# ConnectBox_Charger.net
KiCad netlist of a schematic drawn in EAGLE
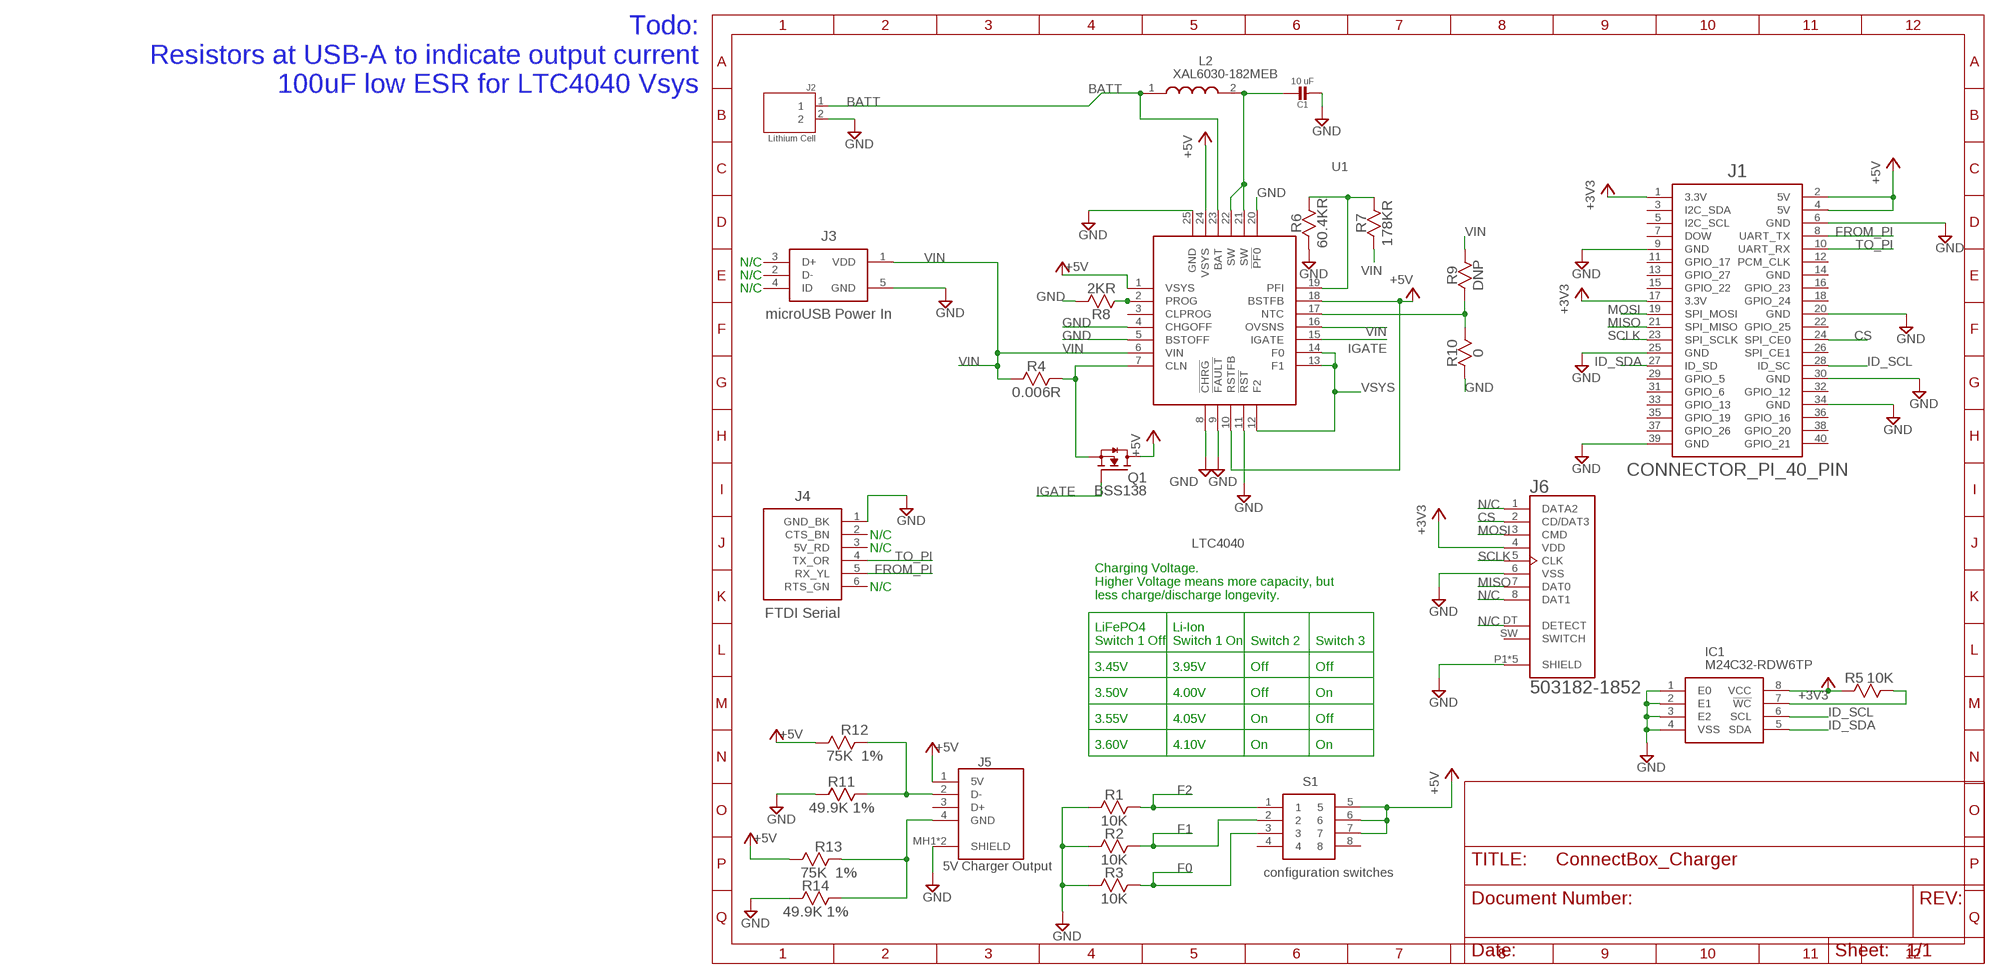
[diagram p0: schematic, sheet 1]

(export (version "E")
  (design (tool "Eeschema 10.0.6"))
  (components
    (comp (ref "C1")
      (value "10 uF")
      (footprint "eagle-import:MICROBUILDER_0805_10MGAP")
      (libsource (lib "eagle-import") (part "MICROBUILDER_CAP_CERAMIC0805_10MGAP"))
    )
    (comp (ref "IC1")
      (value "M24C32-RDW6TP")
      (footprint "eagle-import:SOP65P640X120-8N")
      (fields (field (name "MOUSER_PART_NUMBER") "511-M24C32-RDW6TP"))
      (libsource (lib "eagle-import") (part "M24C32-RDW6TP"))
    )
    (comp (ref "J1")
      (value "CONNECTOR_PI_40_PIN")
      (footprint "eagle-import:2X20")
      (libsource (lib "eagle-import") (part "CONNECTOR_PI_40_PIN"))
    )
    (comp (ref "J2")
      (value "Lithium Cell")
      (footprint "eagle-import:JST_S2B-PH-SM4-TB(LF)(SN)")
      (fields (field (name "MF") "JST Sales") (field (name "MP") "S2B-PH-SM4-TB_LF__SN_"))
      (libsource (lib "eagle-import") (part "S2B-PH-SM4-TB(LF)(SN)"))
    )
    (comp (ref "J3")
      (value "microUSB Power In")
      (footprint "eagle-import:FRAMATOME_10118194-0001LF")
      (fields (field (name "MF") "FCI") (field (name "MP") "10118194-0001LF"))
      (libsource (lib "eagle-import") (part "10118194-0001LF"))
    )
    (comp (ref "J4")
      (value "FTDI Serial")
      (footprint "eagle-import:ESQ-106-XX-X-S")
      (libsource (lib "eagle-import") (part "CONNECTOR-6-FTDI"))
    )
    (comp (ref "J5")
      (value "5V Charger Output")
      (footprint "eagle-import:SS52100001")
      (fields
        (field (name "MANUFACTURER_PART_NUMBER") "SS-52100-001")
        (field (name "MOUSER_PART_NUMBER") "530-SS-52100-001")
      )
      (libsource (lib "eagle-import") (part "SS-52100-001"))
    )
    (comp (ref "J6")
      (value "503182-1852")
      (footprint "eagle-import:MOLEX_503182-1852")
      (fields
        (field (name "DIGI-KEY_PART_NUMBER") "WM12834CT-ND")
        (field (name "MF") "Molex")
        (field (name "MP") "5031821852")
      )
      (libsource (lib "eagle-import") (part "503182-1852"))
    )
    (comp (ref "L2")
      (value "XAL6030-182MEB")
      (footprint "eagle-import:XAL6030182MEB")
      (fields (field (name "MOUSER_PART_NUMBER") "994-XAL6030-182MEB"))
      (libsource (lib "eagle-import") (part "XAL6030-182MEB"))
    )
    (comp (ref "Q1")
      (value "BSS138")
      (footprint "eagle-import:BSS138")
      (fields (field (name "MF") "Fairchild Semiconductor"))
      (libsource (lib "eagle-import") (part "BSS138"))
    )
    (comp (ref "R1")
      (value "10K")
      (footprint "eagle-import:RESC1608X55L25N")
      (libsource (lib "eagle-import") (part "RESISTOR0603"))
    )
    (comp (ref "R2")
      (value "10K")
      (footprint "eagle-import:RESC1608X55L25N")
      (libsource (lib "eagle-import") (part "RESISTOR0603"))
    )
    (comp (ref "R3")
      (value "10K")
      (footprint "eagle-import:RESC1608X55L25N")
      (libsource (lib "eagle-import") (part "RESISTOR0603"))
    )
    (comp (ref "R4")
      (value "0.006R")
      (footprint "eagle-import:RESC1608X55L25N")
      (libsource (lib "eagle-import") (part "RESISTOR0603"))
    )
    (comp (ref "R5")
      (value "10K")
      (footprint "eagle-import:RESC1608X55L25N")
      (libsource (lib "eagle-import") (part "RESISTOR0603"))
    )
    (comp (ref "R6")
      (value "60.4KR")
      (footprint "eagle-import:RESC1608X55L25N")
      (libsource (lib "eagle-import") (part "RESISTOR0603"))
    )
    (comp (ref "R7")
      (value "178KR")
      (footprint "eagle-import:RESC1608X55L25N")
      (libsource (lib "eagle-import") (part "RESISTOR0603"))
    )
    (comp (ref "R8")
      (value "2KR")
      (footprint "eagle-import:RESC1608X55L25N")
      (libsource (lib "eagle-import") (part "RESISTOR0603"))
    )
    (comp (ref "R9")
      (value "DNP")
      (footprint "eagle-import:RESC1608X55L25N")
      (libsource (lib "eagle-import") (part "RESISTOR0603"))
    )
    (comp (ref "R10")
      (value "0")
      (footprint "eagle-import:RESC1608X55L25N")
      (libsource (lib "eagle-import") (part "RESISTOR0603"))
    )
    (comp (ref "R11")
      (value "49.9K 1%")
      (footprint "eagle-import:RESC1608X55L25N")
      (libsource (lib "eagle-import") (part "RESISTOR0603"))
    )
    (comp (ref "R12")
      (value "75K 1%")
      (footprint "eagle-import:RESC1608X55L25N")
      (libsource (lib "eagle-import") (part "RESISTOR0603"))
    )
    (comp (ref "R13")
      (value "75K 1%")
      (footprint "eagle-import:RESC1608X55L25N")
      (libsource (lib "eagle-import") (part "RESISTOR0603"))
    )
    (comp (ref "R14")
      (value "49.9K 1%")
      (footprint "eagle-import:RESC1608X55L25N")
      (libsource (lib "eagle-import") (part "RESISTOR0603"))
    )
    (comp (ref "S1")
      (value "configuration switches")
      (footprint "eagle-import:219-4LPST")
      (fields
        (field (name "MANUFACTURER_PART_NUMBER") "219-4LPST")
        (field (name "MOUSER_PART_NUMBER") "774-2194LPST")
        (field (name "RS_PART_NUMBER") "1774220")
      )
      (libsource (lib "eagle-import") (part "219-4LPST"))
    )
    (comp (ref "U1")
      (value "LTC4040")
      (footprint "eagle-import:QFN50P500X400X80-25N")
      (libsource (lib "eagle-import") (part "LTC4040"))
    )
  )
  (nets
    (net (code "1") (name "+3V3") (class "Default")
      (node (ref "IC1") (pin "8") (pinfunction "VCC_8") (pintype "bidirectional"))
      (node (ref "J1") (pin "1") (pinfunction "3.3V_1") (pintype "bidirectional"))
      (node (ref "J1") (pin "17") (pinfunction "3.3V_17") (pintype "bidirectional"))
      (node (ref "J6") (pin "4") (pinfunction "VDD_4") (pintype "power_in"))
      (node (ref "R5") (pin "2") (pinfunction "2_2") (pintype "bidirectional"))
    )
    (net (code "2") (name "+5V") (class "Default")
      (node (ref "J1") (pin "2") (pinfunction "5V_2") (pintype "bidirectional"))
      (node (ref "J1") (pin "4") (pinfunction "5V_4") (pintype "bidirectional"))
      (node (ref "J5") (pin "1") (pinfunction "5V_1") (pintype "bidirectional"))
      (node (ref "Q1") (pin "D") (pinfunction "D_D") (pintype "passive"))
      (node (ref "R12") (pin "2") (pinfunction "2_2") (pintype "bidirectional"))
      (node (ref "R13") (pin "2") (pinfunction "2_2") (pintype "bidirectional"))
      (node (ref "S1") (pin "5") (pinfunction "5_5") (pintype "bidirectional"))
      (node (ref "S1") (pin "6") (pinfunction "6_6") (pintype "bidirectional"))
      (node (ref "S1") (pin "7") (pinfunction "7_7") (pintype "bidirectional"))
      (node (ref "U1") (pin "1") (pinfunction "VSYS_1") (pintype "bidirectional"))
      (node (ref "U1") (pin "10") (pinfunction "RSTFB_10") (pintype "bidirectional"))
      (node (ref "U1") (pin "18") (pinfunction "BSTFB_18") (pintype "bidirectional"))
      (node (ref "U1") (pin "24") (pinfunction "VSYS_24") (pintype "bidirectional"))
    )
    (net (code "3") (name "/BATT") (class "Default")
      (node (ref "J2") (pin "1") (pinfunction "1_1") (pintype "passive"))
      (node (ref "L2") (pin "1") (pinfunction "1_1") (pintype "bidirectional"))
      (node (ref "U1") (pin "23") (pinfunction "BAT_23") (pintype "bidirectional"))
    )
    (net (code "4") (name "/CS") (class "Default")
      (node (ref "J1") (pin "24") (pinfunction "SPI_CE0_24") (pintype "bidirectional"))
      (node (ref "J6") (pin "2") (pinfunction "CD/DAT3_2") (pintype "bidirectional"))
    )
    (net (code "5") (name "/F0") (class "Default")
      (node (ref "R3") (pin "2") (pinfunction "2_2") (pintype "bidirectional"))
      (node (ref "S1") (pin "3") (pinfunction "3_3") (pintype "bidirectional"))
    )
    (net (code "6") (name "/F1") (class "Default")
      (node (ref "R2") (pin "2") (pinfunction "2_2") (pintype "bidirectional"))
      (node (ref "S1") (pin "2") (pinfunction "2_2") (pintype "bidirectional"))
    )
    (net (code "7") (name "/F2") (class "Default")
      (node (ref "R1") (pin "2") (pinfunction "2_2") (pintype "bidirectional"))
      (node (ref "S1") (pin "1") (pinfunction "1_1") (pintype "bidirectional"))
    )
    (net (code "8") (name "/FROM_PI") (class "Default")
      (node (ref "J1") (pin "8") (pinfunction "UART_TX_8") (pintype "bidirectional"))
      (node (ref "J4") (pin "5") (pinfunction "RX_YL_5") (pintype "bidirectional"))
    )
    (net (code "9") (name "/ID_SCL") (class "Default")
      (node (ref "IC1") (pin "6") (pinfunction "SCL_6") (pintype "bidirectional"))
      (node (ref "J1") (pin "28") (pinfunction "ID_SC_28") (pintype "bidirectional"))
    )
    (net (code "10") (name "/ID_SDA") (class "Default")
      (node (ref "IC1") (pin "5") (pinfunction "SDA_5") (pintype "bidirectional"))
      (node (ref "J1") (pin "27") (pinfunction "ID_SD_27") (pintype "bidirectional"))
    )
    (net (code "11") (name "/IGATE") (class "Default")
      (node (ref "Q1") (pin "G") (pinfunction "G_G") (pintype "passive"))
      (node (ref "U1") (pin "15") (pinfunction "IGATE_15") (pintype "bidirectional"))
    )
    (net (code "12") (name "/MISO") (class "Default")
      (node (ref "J1") (pin "21") (pinfunction "SPI_MISO_21") (pintype "bidirectional"))
      (node (ref "J6") (pin "7") (pinfunction "DAT0_7") (pintype "bidirectional"))
    )
    (net (code "13") (name "/MOSI") (class "Default")
      (node (ref "J1") (pin "19") (pinfunction "SPI_MOSI_19") (pintype "bidirectional"))
      (node (ref "J6") (pin "3") (pinfunction "CMD_3") (pintype "bidirectional"))
    )
    (net (code "14") (name "/N{slash}C") (class "Default")
      (node (ref "J6") (pin "1") (pinfunction "DATA2_1") (pintype "bidirectional"))
      (node (ref "J6") (pin "8") (pinfunction "DAT1_8") (pintype "bidirectional"))
      (node (ref "J6") (pin "DT") (pinfunction "DETECT_DT") (pintype "bidirectional"))
    )
    (net (code "15") (name "/SCLK") (class "Default")
      (node (ref "J1") (pin "23") (pinfunction "SPI_SCLK_23") (pintype "bidirectional"))
      (node (ref "J6") (pin "5") (pinfunction "CLK_5") (pintype "bidirectional"))
    )
    (net (code "16") (name "/TO_PI") (class "Default")
      (node (ref "J1") (pin "10") (pinfunction "UART_RX_10") (pintype "bidirectional"))
      (node (ref "J4") (pin "4") (pinfunction "TX_OR_4") (pintype "bidirectional"))
    )
    (net (code "17") (name "/VIN") (class "Default")
      (node (ref "J3") (pin "1") (pinfunction "VDD_1") (pintype "power_in"))
      (node (ref "R4") (pin "1") (pinfunction "1_1") (pintype "bidirectional"))
      (node (ref "R7") (pin "1") (pinfunction "1_1") (pintype "bidirectional"))
      (node (ref "R9") (pin "2") (pinfunction "2_2") (pintype "bidirectional"))
      (node (ref "U1") (pin "16") (pinfunction "OVSNS_16") (pintype "bidirectional"))
      (node (ref "U1") (pin "6") (pinfunction "VIN_6") (pintype "bidirectional"))
    )
    (net (code "18") (name "/VSYS") (class "Default")
      (node (ref "U1") (pin "12") (pinfunction "F2_12") (pintype "bidirectional"))
      (node (ref "U1") (pin "13") (pinfunction "F1_13") (pintype "bidirectional"))
      (node (ref "U1") (pin "14") (pinfunction "F0_14") (pintype "bidirectional"))
    )
    (net (code "19") (name "GND") (class "Default")
      (node (ref "C1") (pin "2") (pinfunction "2_2") (pintype "passive"))
      (node (ref "IC1") (pin "1") (pinfunction "E0_1") (pintype "bidirectional"))
      (node (ref "IC1") (pin "2") (pinfunction "E1_2") (pintype "bidirectional"))
      (node (ref "IC1") (pin "3") (pinfunction "E2_3") (pintype "bidirectional"))
      (node (ref "IC1") (pin "4") (pinfunction "VSS_4") (pintype "bidirectional"))
      (node (ref "J1") (pin "20") (pinfunction "GND_20") (pintype "bidirectional"))
      (node (ref "J1") (pin "25") (pinfunction "GND_25") (pintype "bidirectional"))
      (node (ref "J1") (pin "30") (pinfunction "GND_30") (pintype "bidirectional"))
      (node (ref "J1") (pin "34") (pinfunction "GND_34") (pintype "bidirectional"))
      (node (ref "J1") (pin "39") (pinfunction "GND_39") (pintype "bidirectional"))
      (node (ref "J1") (pin "6") (pinfunction "GND_6") (pintype "bidirectional"))
      (node (ref "J1") (pin "9") (pinfunction "GND_9") (pintype "bidirectional"))
      (node (ref "J2") (pin "2") (pinfunction "2_2") (pintype "passive"))
      (node (ref "J3") (pin "5") (pinfunction "GND_5") (pintype "power_in"))
      (node (ref "J4") (pin "1") (pinfunction "GND_BK_1") (pintype "bidirectional"))
      (node (ref "J5") (pin "MH1") (pinfunction "SHIELD_MH1") (pintype "bidirectional"))
      (node (ref "J5") (pin "MH2") (pinfunction "SHIELD_MH2") (pintype "bidirectional"))
      (node (ref "J6") (pin "6") (pinfunction "VSS_6") (pintype "power_in"))
      (node (ref "J6") (pin "P1") (pinfunction "SHIELD_P1") (pintype "passive"))
      (node (ref "J6") (pin "P2") (pinfunction "SHIELD_P2") (pintype "passive"))
      (node (ref "J6") (pin "P3") (pinfunction "SHIELD_P3") (pintype "passive"))
      (node (ref "J6") (pin "P4") (pinfunction "SHIELD_P4") (pintype "passive"))
      (node (ref "J6") (pin "P5") (pinfunction "SHIELD_P5") (pintype "passive"))
      (node (ref "R1") (pin "1") (pinfunction "1_1") (pintype "bidirectional"))
      (node (ref "R10") (pin "1") (pinfunction "1_1") (pintype "bidirectional"))
      (node (ref "R11") (pin "2") (pinfunction "2_2") (pintype "bidirectional"))
      (node (ref "R14") (pin "2") (pinfunction "2_2") (pintype "bidirectional"))
      (node (ref "R2") (pin "1") (pinfunction "1_1") (pintype "bidirectional"))
      (node (ref "R3") (pin "1") (pinfunction "1_1") (pintype "bidirectional"))
      (node (ref "R6") (pin "1") (pinfunction "1_1") (pintype "bidirectional"))
      (node (ref "R8") (pin "2") (pinfunction "2_2") (pintype "bidirectional"))
      (node (ref "U1") (pin "11") (pinfunction "~{RST}_11") (pintype "bidirectional"))
      (node (ref "U1") (pin "20") (pinfunction "~{PF0}_20") (pintype "bidirectional"))
      (node (ref "U1") (pin "25") (pinfunction "GND_25") (pintype "bidirectional"))
      (node (ref "U1") (pin "4") (pinfunction "CHGOFF_4") (pintype "bidirectional"))
      (node (ref "U1") (pin "5") (pinfunction "BSTOFF_5") (pintype "bidirectional"))
      (node (ref "U1") (pin "8") (pinfunction "~{CHRG}_8") (pintype "bidirectional"))
      (node (ref "U1") (pin "9") (pinfunction "~{FAULT}_9") (pintype "bidirectional"))
    )
    (net (code "20") (name "Net-(C1-Pad1)") (class "Default")
      (node (ref "C1") (pin "1") (pinfunction "1_1") (pintype "passive"))
      (node (ref "L2") (pin "2") (pinfunction "2_2") (pintype "bidirectional"))
      (node (ref "U1") (pin "21") (pinfunction "SW_21") (pintype "bidirectional"))
      (node (ref "U1") (pin "22") (pinfunction "SW_22") (pintype "bidirectional"))
    )
    (net (code "21") (name "Net-(IC1-~{WC})") (class "Default")
      (node (ref "IC1") (pin "7") (pinfunction "~{WC}_7") (pintype "bidirectional"))
      (node (ref "R5") (pin "1") (pinfunction "1_1") (pintype "bidirectional"))
    )
    (net (code "22") (name "Net-(J5-D-)") (class "Default")
      (node (ref "J5") (pin "2") (pinfunction "D-_2") (pintype "bidirectional"))
      (node (ref "R11") (pin "1") (pinfunction "1_1") (pintype "bidirectional"))
      (node (ref "R12") (pin "1") (pinfunction "1_1") (pintype "bidirectional"))
    )
    (net (code "23") (name "Net-(J5-GND)") (class "Default")
      (node (ref "J5") (pin "4") (pinfunction "GND_4") (pintype "bidirectional"))
      (node (ref "R13") (pin "1") (pinfunction "1_1") (pintype "bidirectional"))
      (node (ref "R14") (pin "1") (pinfunction "1_1") (pintype "bidirectional"))
    )
    (net (code "24") (name "Net-(U1-CLN)") (class "Default")
      (node (ref "Q1") (pin "S") (pinfunction "S_S") (pintype "passive"))
      (node (ref "R4") (pin "2") (pinfunction "2_2") (pintype "bidirectional"))
      (node (ref "U1") (pin "7") (pinfunction "CLN_7") (pintype "bidirectional"))
    )
    (net (code "25") (name "Net-(U1-NTC)") (class "Default")
      (node (ref "R10") (pin "2") (pinfunction "2_2") (pintype "bidirectional"))
      (node (ref "R9") (pin "1") (pinfunction "1_1") (pintype "bidirectional"))
      (node (ref "U1") (pin "17") (pinfunction "NTC_17") (pintype "bidirectional"))
    )
    (net (code "26") (name "Net-(U1-PFI)") (class "Default")
      (node (ref "R6") (pin "2") (pinfunction "2_2") (pintype "bidirectional"))
      (node (ref "R7") (pin "2") (pinfunction "2_2") (pintype "bidirectional"))
      (node (ref "U1") (pin "19") (pinfunction "PFI_19") (pintype "bidirectional"))
    )
    (net (code "27") (name "Net-(U1-PROG)") (class "Default")
      (node (ref "R8") (pin "1") (pinfunction "1_1") (pintype "bidirectional"))
      (node (ref "U1") (pin "2") (pinfunction "PROG_2") (pintype "bidirectional"))
    )
    (net (code "28") (name "unconnected-(J1-DOW-Pad7)") (class "Default")
      (node (ref "J1") (pin "7") (pinfunction "DOW_7") (pintype "bidirectional"))
    )
    (net (code "29") (name "unconnected-(J1-GND-Pad14)") (class "Default")
      (node (ref "J1") (pin "14") (pinfunction "GND_14") (pintype "bidirectional"))
    )
    (net (code "30") (name "unconnected-(J1-GPIO_5-Pad29)") (class "Default")
      (node (ref "J1") (pin "29") (pinfunction "GPIO_5_29") (pintype "bidirectional"))
    )
    (net (code "31") (name "unconnected-(J1-GPIO_6-Pad31)") (class "Default")
      (node (ref "J1") (pin "31") (pinfunction "GPIO_6_31") (pintype "bidirectional"))
    )
    (net (code "32") (name "unconnected-(J1-GPIO_12-Pad32)") (class "Default")
      (node (ref "J1") (pin "32") (pinfunction "GPIO_12_32") (pintype "bidirectional"))
    )
    (net (code "33") (name "unconnected-(J1-GPIO_13-Pad33)") (class "Default")
      (node (ref "J1") (pin "33") (pinfunction "GPIO_13_33") (pintype "bidirectional"))
    )
    (net (code "34") (name "unconnected-(J1-GPIO_16-Pad36)") (class "Default")
      (node (ref "J1") (pin "36") (pinfunction "GPIO_16_36") (pintype "bidirectional"))
    )
    (net (code "35") (name "unconnected-(J1-GPIO_17-Pad11)") (class "Default")
      (node (ref "J1") (pin "11") (pinfunction "GPIO_17_11") (pintype "bidirectional"))
    )
    (net (code "36") (name "unconnected-(J1-GPIO_19-Pad35)") (class "Default")
      (node (ref "J1") (pin "35") (pinfunction "GPIO_19_35") (pintype "bidirectional"))
    )
    (net (code "37") (name "unconnected-(J1-GPIO_20-Pad38)") (class "Default")
      (node (ref "J1") (pin "38") (pinfunction "GPIO_20_38") (pintype "bidirectional"))
    )
    (net (code "38") (name "unconnected-(J1-GPIO_21-Pad40)") (class "Default")
      (node (ref "J1") (pin "40") (pinfunction "GPIO_21_40") (pintype "bidirectional"))
    )
    (net (code "39") (name "unconnected-(J1-GPIO_22-Pad15)") (class "Default")
      (node (ref "J1") (pin "15") (pinfunction "GPIO_22_15") (pintype "bidirectional"))
    )
    (net (code "40") (name "unconnected-(J1-GPIO_23-Pad16)") (class "Default")
      (node (ref "J1") (pin "16") (pinfunction "GPIO_23_16") (pintype "bidirectional"))
    )
    (net (code "41") (name "unconnected-(J1-GPIO_24-Pad18)") (class "Default")
      (node (ref "J1") (pin "18") (pinfunction "GPIO_24_18") (pintype "bidirectional"))
    )
    (net (code "42") (name "unconnected-(J1-GPIO_25-Pad22)") (class "Default")
      (node (ref "J1") (pin "22") (pinfunction "GPIO_25_22") (pintype "bidirectional"))
    )
    (net (code "43") (name "unconnected-(J1-GPIO_26-Pad37)") (class "Default")
      (node (ref "J1") (pin "37") (pinfunction "GPIO_26_37") (pintype "bidirectional"))
    )
    (net (code "44") (name "unconnected-(J1-GPIO_27-Pad13)") (class "Default")
      (node (ref "J1") (pin "13") (pinfunction "GPIO_27_13") (pintype "bidirectional"))
    )
    (net (code "45") (name "unconnected-(J1-I2C_SCL-Pad5)") (class "Default")
      (node (ref "J1") (pin "5") (pinfunction "I2C_SCL_5") (pintype "bidirectional"))
    )
    (net (code "46") (name "unconnected-(J1-I2C_SDA-Pad3)") (class "Default")
      (node (ref "J1") (pin "3") (pinfunction "I2C_SDA_3") (pintype "bidirectional"))
    )
    (net (code "47") (name "unconnected-(J1-PCM_CLK-Pad12)") (class "Default")
      (node (ref "J1") (pin "12") (pinfunction "PCM_CLK_12") (pintype "bidirectional"))
    )
    (net (code "48") (name "unconnected-(J1-SPI_CE1-Pad26)") (class "Default")
      (node (ref "J1") (pin "26") (pinfunction "SPI_CE1_26") (pintype "bidirectional"))
    )
    (net (code "49") (name "unconnected-(J3-D+-Pad3)") (class "Default")
      (node (ref "J3") (pin "3") (pinfunction "D+_3") (pintype "bidirectional"))
    )
    (net (code "50") (name "unconnected-(J3-D--Pad2)") (class "Default")
      (node (ref "J3") (pin "2") (pinfunction "D-_2") (pintype "bidirectional"))
    )
    (net (code "51") (name "unconnected-(J3-ID-Pad4)") (class "Default")
      (node (ref "J3") (pin "4") (pinfunction "ID_4") (pintype "passive"))
    )
    (net (code "52") (name "unconnected-(J4-5V_RD-Pad3)") (class "Default")
      (node (ref "J4") (pin "3") (pinfunction "5V_RD_3") (pintype "bidirectional"))
    )
    (net (code "53") (name "unconnected-(J4-CTS_BN-Pad2)") (class "Default")
      (node (ref "J4") (pin "2") (pinfunction "CTS_BN_2") (pintype "bidirectional"))
    )
    (net (code "54") (name "unconnected-(J4-RTS_GN-Pad6)") (class "Default")
      (node (ref "J4") (pin "6") (pinfunction "RTS_GN_6") (pintype "bidirectional"))
    )
    (net (code "55") (name "unconnected-(J5-D+-Pad3)") (class "Default")
      (node (ref "J5") (pin "3") (pinfunction "D+_3") (pintype "bidirectional"))
    )
    (net (code "56") (name "unconnected-(J6-SWITCH-PadSW)") (class "Default")
      (node (ref "J6") (pin "SW") (pinfunction "SWITCH_SW") (pintype "bidirectional"))
    )
    (net (code "57") (name "unconnected-(S1-Pad4)") (class "Default")
      (node (ref "S1") (pin "4") (pinfunction "4_4") (pintype "bidirectional"))
    )
    (net (code "58") (name "unconnected-(S1-Pad8)") (class "Default")
      (node (ref "S1") (pin "8") (pinfunction "8_8") (pintype "bidirectional"))
    )
    (net (code "59") (name "unconnected-(U1-CLPROG-Pad3)") (class "Default")
      (node (ref "U1") (pin "3") (pinfunction "CLPROG_3") (pintype "bidirectional"))
    )
  )
)
